# Schematic.net
KiCad netlist of a schematic drawn in EAGLE
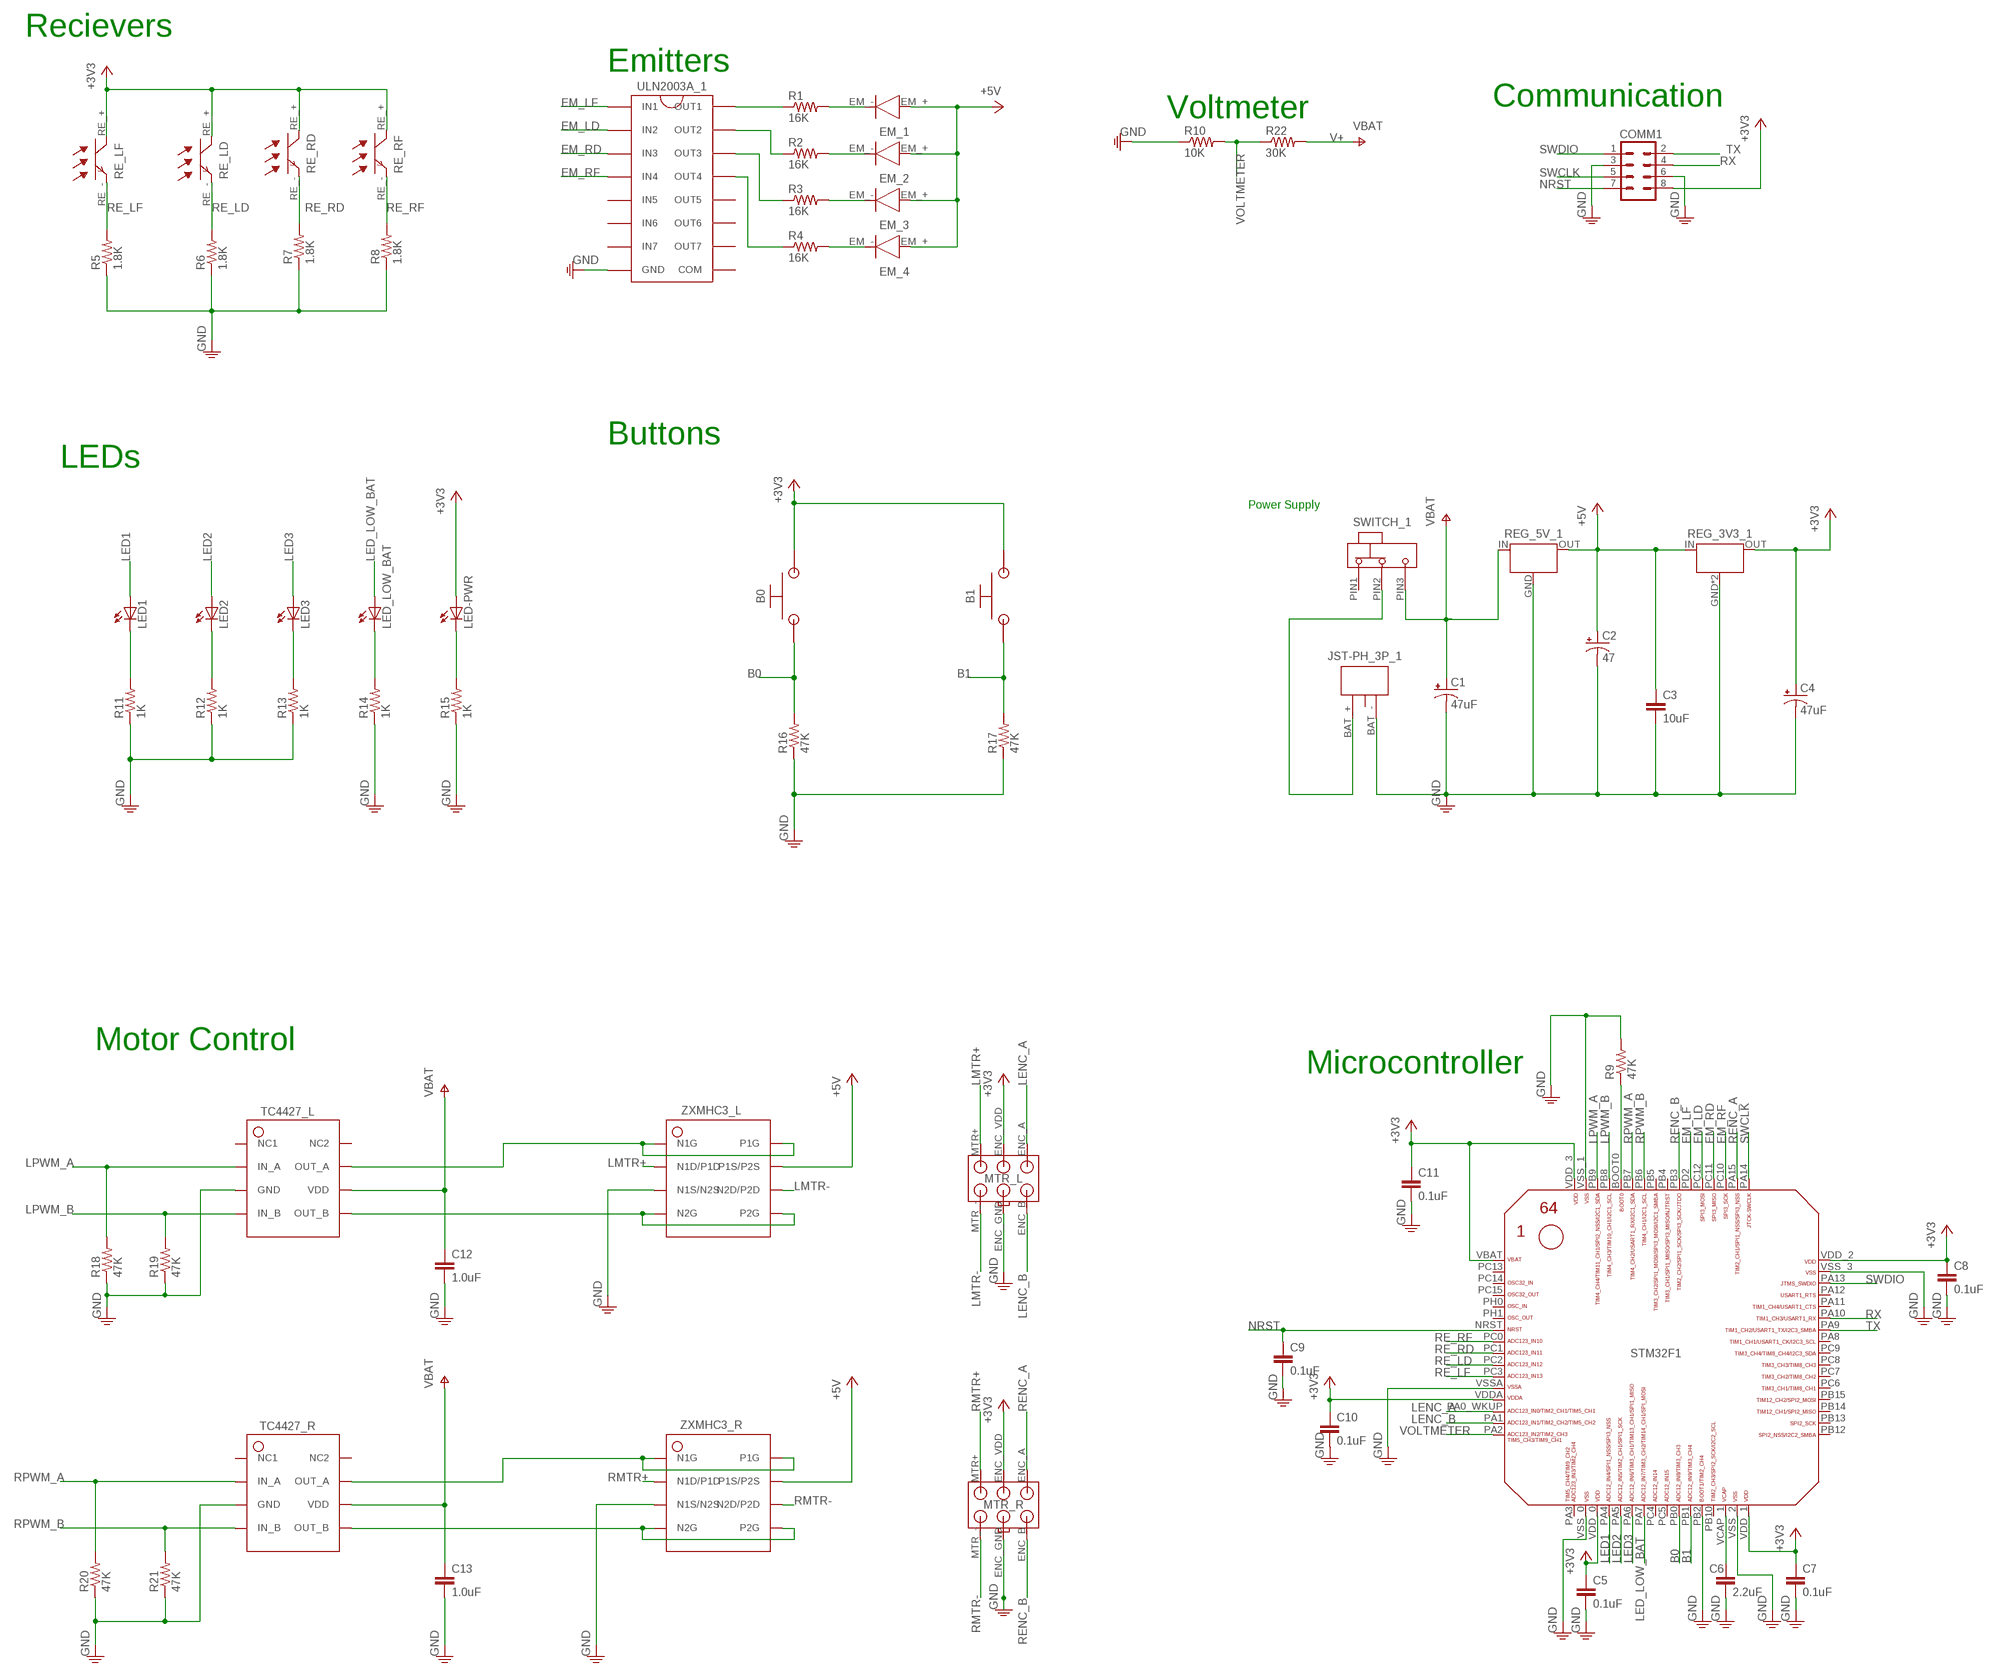
[diagram p0: schematic, sheet 1]

(export (version "E")
  (design (tool "Eeschema 10.0.6"))
  (components
    (comp (ref "B0")
      (value "POLOLU_BUTTON")
      (footprint "eagle-import:POLOLU_BUTTON")
      (libsource (lib "eagle-import") (part "POLOLU_BUTTON"))
    )
    (comp (ref "B1")
      (value "POLOLU_BUTTON")
      (footprint "eagle-import:POLOLU_BUTTON")
      (libsource (lib "eagle-import") (part "POLOLU_BUTTON"))
    )
    (comp (ref "C1")
      (value "47uF")
      (footprint "eagle-import:CAP_TANT_1210IN_3528MM")
      (libsource (lib "eagle-import") (part "CAP_TANT_1210IN_3528MM"))
    )
    (comp (ref "C2")
      (value "47")
      (footprint "eagle-import:CAP_TANT_1210IN_3528MM")
      (libsource (lib "eagle-import") (part "CAP_TANT_1210IN_3528MM"))
    )
    (comp (ref "C3")
      (value "10uF")
      (footprint "eagle-import:0805")
      (libsource (lib "eagle-import") (part "CAP_CERAMIC_0805IN_2012MM"))
    )
    (comp (ref "C4")
      (value "47uF")
      (footprint "eagle-import:CAP_TANT_1210IN_3528MM")
      (libsource (lib "eagle-import") (part "CAP_TANT_1210IN_3528MM"))
    )
    (comp (ref "C5")
      (value "0.1uF")
      (footprint "eagle-import:0805")
      (libsource (lib "eagle-import") (part "CAP_CERAMIC_0805IN_2012MM"))
    )
    (comp (ref "C6")
      (value "2.2uF")
      (footprint "eagle-import:0805")
      (libsource (lib "eagle-import") (part "CAP_CERAMIC_0805IN_2012MM"))
    )
    (comp (ref "C7")
      (value "0.1uF")
      (footprint "eagle-import:0805")
      (libsource (lib "eagle-import") (part "CAP_CERAMIC_0805IN_2012MM"))
    )
    (comp (ref "C8")
      (value "0.1uF")
      (footprint "eagle-import:0805")
      (libsource (lib "eagle-import") (part "CAP_CERAMIC_0805IN_2012MM"))
    )
    (comp (ref "C9")
      (value "0.1uF")
      (footprint "eagle-import:0805")
      (libsource (lib "eagle-import") (part "CAP_CERAMIC_0805IN_2012MM"))
    )
    (comp (ref "C10")
      (value "0.1uF")
      (footprint "eagle-import:0805")
      (libsource (lib "eagle-import") (part "CAP_CERAMIC_0805IN_2012MM"))
    )
    (comp (ref "C11")
      (value "0.1uF")
      (footprint "eagle-import:0805")
      (libsource (lib "eagle-import") (part "CAP_CERAMIC_0805IN_2012MM"))
    )
    (comp (ref "C12")
      (value "1.0uF")
      (footprint "eagle-import:0805")
      (libsource (lib "eagle-import") (part "CAP_CERAMIC_0805IN_2012MM"))
    )
    (comp (ref "C13")
      (value "1.0uF")
      (footprint "eagle-import:0805")
      (libsource (lib "eagle-import") (part "CAP_CERAMIC_0805IN_2012MM"))
    )
    (comp (ref "COMM1")
      (value "M04X2")
      (footprint "eagle-import:2X4")
      (libsource (lib "eagle-import") (part "M04X2"))
    )
    (comp (ref "EM_1")
      (value "SFH4545")
      (footprint "eagle-import:EMITTER")
      (libsource (lib "eagle-import") (part "SFH4545"))
    )
    (comp (ref "EM_2")
      (value "SFH4545")
      (footprint "eagle-import:EMITTER")
      (libsource (lib "eagle-import") (part "SFH4545"))
    )
    (comp (ref "EM_3")
      (value "SFH4545")
      (footprint "eagle-import:EMITTER")
      (libsource (lib "eagle-import") (part "SFH4545"))
    )
    (comp (ref "EM_4")
      (value "SFH4545")
      (footprint "eagle-import:EMITTER")
      (libsource (lib "eagle-import") (part "SFH4545"))
    )
    (comp (ref "JST-PH_3P_1")
      (value "3PIN")
      (footprint "eagle-import:B3B-PH-K-S")
      (libsource (lib "eagle-import") (part "3PIN"))
    )
    (comp (ref "LED-PWR")
      (value "LED")
      (footprint "eagle-import:LED-0805")
      (libsource (lib "eagle-import") (part "LED"))
    )
    (comp (ref "LED1")
      (value "LED")
      (footprint "eagle-import:LED-0805")
      (libsource (lib "eagle-import") (part "LED"))
    )
    (comp (ref "LED2")
      (value "LED")
      (footprint "eagle-import:LED-0805")
      (libsource (lib "eagle-import") (part "LED"))
    )
    (comp (ref "LED3")
      (value "LED")
      (footprint "eagle-import:LED-0805")
      (libsource (lib "eagle-import") (part "LED"))
    )
    (comp (ref "LED_LOW_BAT")
      (value "LED")
      (footprint "eagle-import:LED-0805")
      (libsource (lib "eagle-import") (part "LED"))
    )
    (comp (ref "MTR_L")
      (value "MOTOR_ENCODER_HEADER")
      (footprint "eagle-import:MOTOR_ENCODER_HEADER")
      (libsource (lib "eagle-import") (part "MOTOR_ENCODER_HEADER"))
    )
    (comp (ref "MTR_R")
      (value "MOTOR_ENCODER_HEADER")
      (footprint "eagle-import:MOTOR_ENCODER_HEADER")
      (libsource (lib "eagle-import") (part "MOTOR_ENCODER_HEADER"))
    )
    (comp (ref "R1")
      (value "16K")
      (footprint "eagle-import:0805")
      (libsource (lib "eagle-import") (part "RESISTOR_0805IN_2012MM"))
    )
    (comp (ref "R2")
      (value "16K")
      (footprint "eagle-import:0805")
      (libsource (lib "eagle-import") (part "RESISTOR_0805IN_2012MM"))
    )
    (comp (ref "R3")
      (value "16K")
      (footprint "eagle-import:0805")
      (libsource (lib "eagle-import") (part "RESISTOR_0805IN_2012MM"))
    )
    (comp (ref "R4")
      (value "16K")
      (footprint "eagle-import:0805")
      (libsource (lib "eagle-import") (part "RESISTOR_0805IN_2012MM"))
    )
    (comp (ref "R5")
      (value "1.8K")
      (footprint "eagle-import:0805")
      (libsource (lib "eagle-import") (part "RESISTOR_0805IN_2012MM"))
    )
    (comp (ref "R6")
      (value "1.8K")
      (footprint "eagle-import:0805")
      (libsource (lib "eagle-import") (part "RESISTOR_0805IN_2012MM"))
    )
    (comp (ref "R7")
      (value "1.8K")
      (footprint "eagle-import:0805")
      (libsource (lib "eagle-import") (part "RESISTOR_0805IN_2012MM"))
    )
    (comp (ref "R8")
      (value "1.8K")
      (footprint "eagle-import:0805")
      (libsource (lib "eagle-import") (part "RESISTOR_0805IN_2012MM"))
    )
    (comp (ref "R9")
      (value "47K")
      (footprint "eagle-import:0805")
      (libsource (lib "eagle-import") (part "RESISTOR_0805IN_2012MM"))
    )
    (comp (ref "R10")
      (value "10K")
      (footprint "eagle-import:0805")
      (libsource (lib "eagle-import") (part "RESISTOR_0805IN_2012MM"))
    )
    (comp (ref "R11")
      (value "1K")
      (footprint "eagle-import:0805")
      (libsource (lib "eagle-import") (part "RESISTOR_0805IN_2012MM"))
    )
    (comp (ref "R12")
      (value "1K")
      (footprint "eagle-import:0805")
      (libsource (lib "eagle-import") (part "RESISTOR_0805IN_2012MM"))
    )
    (comp (ref "R13")
      (value "1K")
      (footprint "eagle-import:0805")
      (libsource (lib "eagle-import") (part "RESISTOR_0805IN_2012MM"))
    )
    (comp (ref "R14")
      (value "1K")
      (footprint "eagle-import:0805")
      (libsource (lib "eagle-import") (part "RESISTOR_0805IN_2012MM"))
    )
    (comp (ref "R15")
      (value "1K")
      (footprint "eagle-import:0805")
      (libsource (lib "eagle-import") (part "RESISTOR_0805IN_2012MM"))
    )
    (comp (ref "R16")
      (value "47K")
      (footprint "eagle-import:0805")
      (libsource (lib "eagle-import") (part "RESISTOR_0805IN_2012MM"))
    )
    (comp (ref "R17")
      (value "47K")
      (footprint "eagle-import:0805")
      (libsource (lib "eagle-import") (part "RESISTOR_0805IN_2012MM"))
    )
    (comp (ref "R18")
      (value "47K")
      (footprint "eagle-import:0805")
      (libsource (lib "eagle-import") (part "RESISTOR_0805IN_2012MM"))
    )
    (comp (ref "R19")
      (value "47K")
      (footprint "eagle-import:0805")
      (libsource (lib "eagle-import") (part "RESISTOR_0805IN_2012MM"))
    )
    (comp (ref "R20")
      (value "47K")
      (footprint "eagle-import:0805")
      (libsource (lib "eagle-import") (part "RESISTOR_0805IN_2012MM"))
    )
    (comp (ref "R21")
      (value "47K")
      (footprint "eagle-import:0805")
      (libsource (lib "eagle-import") (part "RESISTOR_0805IN_2012MM"))
    )
    (comp (ref "R22")
      (value "30K")
      (footprint "eagle-import:0805")
      (libsource (lib "eagle-import") (part "RESISTOR_0805IN_2012MM"))
    )
    (comp (ref "REG_3V3_1")
      (value "3V3_REG")
      (footprint "eagle-import:SOT223")
      (libsource (lib "eagle-import") (part "3V3_REG"))
    )
    (comp (ref "REG_5V_1")
      (value "REG_5V_MURATA")
      (footprint "eagle-import:5V_REG_MURATA")
      (libsource (lib "eagle-import") (part "REG_5V_MURATA"))
    )
    (comp (ref "RE_LD")
      (value "TEFT4300")
      (footprint "eagle-import:RECEIVER")
      (libsource (lib "eagle-import") (part "TEFT4300"))
    )
    (comp (ref "RE_LF")
      (value "TEFT4300")
      (footprint "eagle-import:RECEIVER")
      (libsource (lib "eagle-import") (part "TEFT4300"))
    )
    (comp (ref "RE_RD")
      (value "TEFT4300")
      (footprint "eagle-import:RECEIVER")
      (libsource (lib "eagle-import") (part "TEFT4300"))
    )
    (comp (ref "RE_RF")
      (value "TEFT4300")
      (footprint "eagle-import:RECEIVER")
      (libsource (lib "eagle-import") (part "TEFT4300"))
    )
    (comp (ref "STM32F1")
      (value "STM32F4_401_410_411_412_413_446")
      (footprint "eagle-import:LQFP64")
      (libsource (lib "eagle-import") (part "STM32F4_401_410_411_412_413_446"))
    )
    (comp (ref "SWITCH_1")
      (value "POLOLU_SWITCH")
      (footprint "eagle-import:POLOLU_SWITCH")
      (libsource (lib "eagle-import") (part "POLOLU_SWITCH"))
    )
    (comp (ref "TC4427_L")
      (value "TC4427_SOIC8")
      (footprint "eagle-import:TC4427_SOIC8")
      (libsource (lib "eagle-import") (part "TC4427_SOIC8"))
    )
    (comp (ref "TC4427_R")
      (value "TC4427_SOIC8")
      (footprint "eagle-import:TC4427_SOIC8")
      (libsource (lib "eagle-import") (part "TC4427_SOIC8"))
    )
    (comp (ref "ULN2003A_1")
      (value "ULN2003A")
      (footprint "eagle-import:ULN2003A")
      (libsource (lib "eagle-import") (part "ULN2003A"))
    )
    (comp (ref "ZXMHC3_L")
      (value "ZXMHC3")
      (footprint "eagle-import:ZXMHC3")
      (libsource (lib "eagle-import") (part "ZXMHC3"))
    )
    (comp (ref "ZXMHC3_R")
      (value "ZXMHC3")
      (footprint "eagle-import:ZXMHC3")
      (libsource (lib "eagle-import") (part "ZXMHC3"))
    )
  )
  (nets
    (net (code "1") (name "+3V3") (class "Default")
      (node (ref "B0") (pin "P$2") (pinfunction "2_P$2") (pintype "bidirectional"))
      (node (ref "B1") (pin "P$2") (pinfunction "2_P$2") (pintype "bidirectional"))
      (node (ref "C10") (pin "1") (pinfunction "1_1") (pintype "passive"))
      (node (ref "C11") (pin "1") (pinfunction "1_1") (pintype "passive"))
      (node (ref "C4") (pin "A") (pinfunction "+_A") (pintype "passive"))
      (node (ref "C5") (pin "1") (pinfunction "1_1") (pintype "passive"))
      (node (ref "C7") (pin "1") (pinfunction "1_1") (pintype "passive"))
      (node (ref "C8") (pin "1") (pinfunction "1_1") (pintype "passive"))
      (node (ref "COMM1") (pin "8") (pinfunction "8_8") (pintype "passive"))
      (node (ref "LED-PWR") (pin "A") (pinfunction "A_A") (pintype "passive"))
      (node (ref "MTR_L") (pin "ENC_VDD") (pinfunction "ENC_VDD_ENC_VDD") (pintype "power_in"))
      (node (ref "MTR_R") (pin "ENC_VDD") (pinfunction "ENC_VDD_ENC_VDD") (pintype "power_in"))
      (node (ref "REG_3V3_1") (pin "OUT") (pinfunction "OUT_OUT") (pintype "power_in"))
      (node (ref "RE_LD") (pin "RE_+") (pinfunction "C_RE_+") (pintype "bidirectional"))
      (node (ref "RE_LF") (pin "RE_+") (pinfunction "C_RE_+") (pintype "bidirectional"))
      (node (ref "RE_RD") (pin "RE_+") (pinfunction "C_RE_+") (pintype "bidirectional"))
      (node (ref "RE_RF") (pin "RE_+") (pinfunction "C_RE_+") (pintype "bidirectional"))
      (node (ref "STM32F1") (pin "VBAT") (pinfunction "VBAT_VBAT") (pintype "power_in"))
      (node (ref "STM32F1") (pin "VDDA") (pinfunction "VDDA_VDDA") (pintype "power_in"))
      (node (ref "STM32F1") (pin "VDD_0") (pinfunction "VDD_0_VDD_0") (pintype "power_in"))
      (node (ref "STM32F1") (pin "VDD_1") (pinfunction "VDD_1_VDD_1") (pintype "power_in"))
      (node (ref "STM32F1") (pin "VDD_2") (pinfunction "VDD_2_VDD_2") (pintype "power_in"))
      (node (ref "STM32F1") (pin "VDD_3") (pinfunction "VDD_3_VDD_3") (pintype "power_in"))
    )
    (net (code "2") (name "+5V") (class "Default")
      (node (ref "C2") (pin "A") (pinfunction "+_A") (pintype "passive"))
      (node (ref "C3") (pin "1") (pinfunction "1_1") (pintype "passive"))
      (node (ref "EM_1") (pin "EM_+") (pinfunction "+_EM_+") (pintype "bidirectional"))
      (node (ref "EM_2") (pin "EM_+") (pinfunction "+_EM_+") (pintype "bidirectional"))
      (node (ref "EM_3") (pin "EM_+") (pinfunction "+_EM_+") (pintype "bidirectional"))
      (node (ref "EM_4") (pin "EM_+") (pinfunction "+_EM_+") (pintype "bidirectional"))
      (node (ref "REG_3V3_1") (pin "IN") (pinfunction "IN_IN") (pintype "power_in"))
      (node (ref "REG_5V_1") (pin "OUT") (pinfunction "OUT_OUT") (pintype "power_in"))
      (node (ref "ZXMHC3_L") (pin "P1S/P2S") (pinfunction "P1S/P2S_P1S/P2S") (pintype "bidirectional"))
      (node (ref "ZXMHC3_R") (pin "P1S/P2S") (pinfunction "P1S/P2S_P1S/P2S") (pintype "bidirectional"))
    )
    (net (code "3") (name "/B0") (class "Default")
      (node (ref "B0") (pin "P$1") (pinfunction "1_P$1") (pintype "bidirectional"))
      (node (ref "R16") (pin "2") (pinfunction "2_2") (pintype "passive"))
      (node (ref "STM32F1") (pin "PB0") (pinfunction "PB0_PB0") (pintype "bidirectional"))
    )
    (net (code "4") (name "/B1") (class "Default")
      (node (ref "B1") (pin "P$1") (pinfunction "1_P$1") (pintype "bidirectional"))
      (node (ref "R17") (pin "2") (pinfunction "2_2") (pintype "passive"))
      (node (ref "STM32F1") (pin "PB1") (pinfunction "PB1_PB1") (pintype "bidirectional"))
    )
    (net (code "5") (name "/EM_LD") (class "Default")
      (node (ref "STM32F1") (pin "PC12") (pinfunction "PC12_PC12") (pintype "bidirectional"))
      (node (ref "ULN2003A_1") (pin "2B") (pinfunction "IN2_2B") (pintype "bidirectional"))
    )
    (net (code "6") (name "/EM_LF") (class "Default")
      (node (ref "STM32F1") (pin "PD2") (pinfunction "PD2_PD2") (pintype "bidirectional"))
      (node (ref "ULN2003A_1") (pin "1B") (pinfunction "IN1_1B") (pintype "bidirectional"))
    )
    (net (code "7") (name "/EM_RD") (class "Default")
      (node (ref "STM32F1") (pin "PC11") (pinfunction "PC11_PC11") (pintype "bidirectional"))
      (node (ref "ULN2003A_1") (pin "3B") (pinfunction "IN3_3B") (pintype "bidirectional"))
    )
    (net (code "8") (name "/EM_RF") (class "Default")
      (node (ref "STM32F1") (pin "PC10") (pinfunction "PC10_PC10") (pintype "bidirectional"))
      (node (ref "ULN2003A_1") (pin "4B") (pinfunction "IN4_4B") (pintype "bidirectional"))
    )
    (net (code "9") (name "/LED1") (class "Default")
      (node (ref "LED1") (pin "A") (pinfunction "A_A") (pintype "passive"))
      (node (ref "STM32F1") (pin "PA4") (pinfunction "PA4_PA4") (pintype "bidirectional"))
    )
    (net (code "10") (name "/LED2") (class "Default")
      (node (ref "LED2") (pin "A") (pinfunction "A_A") (pintype "passive"))
      (node (ref "STM32F1") (pin "PA5") (pinfunction "PA5_PA5") (pintype "bidirectional"))
    )
    (net (code "11") (name "/LED3") (class "Default")
      (node (ref "LED3") (pin "A") (pinfunction "A_A") (pintype "passive"))
      (node (ref "STM32F1") (pin "PA6") (pinfunction "PA6_PA6") (pintype "bidirectional"))
    )
    (net (code "12") (name "/LED_LOW_BAT") (class "Default")
      (node (ref "LED_LOW_BAT") (pin "A") (pinfunction "A_A") (pintype "passive"))
      (node (ref "STM32F1") (pin "PA7") (pinfunction "PA7_PA7") (pintype "bidirectional"))
    )
    (net (code "13") (name "/LENC_A") (class "Default")
      (node (ref "MTR_L") (pin "ENC_A") (pinfunction "ENC_A_ENC_A") (pintype "output"))
      (node (ref "STM32F1") (pin "PA0_WKUP") (pinfunction "PA0_AKUP_PA0_WKUP") (pintype "bidirectional"))
    )
    (net (code "14") (name "/LENC_B") (class "Default")
      (node (ref "MTR_L") (pin "ENC_B") (pinfunction "ENC_B_ENC_B") (pintype "output"))
      (node (ref "STM32F1") (pin "PA1") (pinfunction "PA1_PA1") (pintype "bidirectional"))
    )
    (net (code "15") (name "/LMTR+") (class "Default")
      (node (ref "MTR_L") (pin "MTR+") (pinfunction "MTR_+_MTR+") (pintype "input"))
      (node (ref "ZXMHC3_L") (pin "N1D/P1D") (pinfunction "N1D/P1D_N1D/P1D") (pintype "bidirectional"))
    )
    (net (code "16") (name "/LMTR-") (class "Default")
      (node (ref "MTR_L") (pin "MTR_-") (pinfunction "MTR_-_MTR_-") (pintype "input"))
      (node (ref "ZXMHC3_L") (pin "N2D/P2D") (pinfunction "N2D/P2D_N2D/P2D") (pintype "bidirectional"))
    )
    (net (code "17") (name "/LPWM_A") (class "Default")
      (node (ref "R18") (pin "2") (pinfunction "2_2") (pintype "passive"))
      (node (ref "STM32F1") (pin "PB9") (pinfunction "PB9_PB9") (pintype "bidirectional"))
      (node (ref "TC4427_L") (pin "IN_A") (pinfunction "IN_A_IN_A") (pintype "bidirectional"))
    )
    (net (code "18") (name "/LPWM_B") (class "Default")
      (node (ref "R19") (pin "2") (pinfunction "2_2") (pintype "passive"))
      (node (ref "STM32F1") (pin "PB8") (pinfunction "PB8_PB8") (pintype "bidirectional"))
      (node (ref "TC4427_L") (pin "IN_B") (pinfunction "IN_B_IN_B") (pintype "bidirectional"))
    )
    (net (code "19") (name "/NRST") (class "Default")
      (node (ref "C9") (pin "1") (pinfunction "1_1") (pintype "passive"))
      (node (ref "COMM1") (pin "7") (pinfunction "7_7") (pintype "passive"))
      (node (ref "STM32F1") (pin "NRST") (pinfunction "NRST_NRST") (pintype "bidirectional"))
    )
    (net (code "20") (name "/RENC_A") (class "Default")
      (node (ref "MTR_R") (pin "ENC_A") (pinfunction "ENC_A_ENC_A") (pintype "output"))
      (node (ref "STM32F1") (pin "PA15") (pinfunction "PA15_PA15") (pintype "bidirectional"))
    )
    (net (code "21") (name "/RENC_B") (class "Default")
      (node (ref "MTR_R") (pin "ENC_B") (pinfunction "ENC_B_ENC_B") (pintype "output"))
      (node (ref "STM32F1") (pin "PB3") (pinfunction "PB3_PB3") (pintype "bidirectional"))
    )
    (net (code "22") (name "/RE_LD") (class "Default")
      (node (ref "R6") (pin "2") (pinfunction "2_2") (pintype "passive"))
      (node (ref "RE_LD") (pin "RE_-") (pinfunction "E_RE_-") (pintype "bidirectional"))
      (node (ref "STM32F1") (pin "PC2") (pinfunction "PC2_PC2") (pintype "bidirectional"))
    )
    (net (code "23") (name "/RE_LF") (class "Default")
      (node (ref "R5") (pin "2") (pinfunction "2_2") (pintype "passive"))
      (node (ref "RE_LF") (pin "RE_-") (pinfunction "E_RE_-") (pintype "bidirectional"))
      (node (ref "STM32F1") (pin "PC3") (pinfunction "PC3_PC3") (pintype "bidirectional"))
    )
    (net (code "24") (name "/RE_RD") (class "Default")
      (node (ref "R7") (pin "2") (pinfunction "2_2") (pintype "passive"))
      (node (ref "RE_RD") (pin "RE_-") (pinfunction "E_RE_-") (pintype "bidirectional"))
      (node (ref "STM32F1") (pin "PC1") (pinfunction "PC1_PC1") (pintype "bidirectional"))
    )
    (net (code "25") (name "/RE_RF") (class "Default")
      (node (ref "R8") (pin "2") (pinfunction "2_2") (pintype "passive"))
      (node (ref "RE_RF") (pin "RE_-") (pinfunction "E_RE_-") (pintype "bidirectional"))
      (node (ref "STM32F1") (pin "PC0") (pinfunction "PC0_PC0") (pintype "bidirectional"))
    )
    (net (code "26") (name "/RMTR+") (class "Default")
      (node (ref "MTR_R") (pin "MTR+") (pinfunction "MTR_+_MTR+") (pintype "input"))
      (node (ref "ZXMHC3_R") (pin "N1D/P1D") (pinfunction "N1D/P1D_N1D/P1D") (pintype "bidirectional"))
    )
    (net (code "27") (name "/RMTR-") (class "Default")
      (node (ref "MTR_R") (pin "MTR_-") (pinfunction "MTR_-_MTR_-") (pintype "input"))
      (node (ref "ZXMHC3_R") (pin "N2D/P2D") (pinfunction "N2D/P2D_N2D/P2D") (pintype "bidirectional"))
    )
    (net (code "28") (name "/RPWM_A") (class "Default")
      (node (ref "R20") (pin "2") (pinfunction "2_2") (pintype "passive"))
      (node (ref "STM32F1") (pin "PB7") (pinfunction "PB7_PB7") (pintype "bidirectional"))
      (node (ref "TC4427_R") (pin "IN_A") (pinfunction "IN_A_IN_A") (pintype "bidirectional"))
    )
    (net (code "29") (name "/RPWM_B") (class "Default")
      (node (ref "R21") (pin "2") (pinfunction "2_2") (pintype "passive"))
      (node (ref "STM32F1") (pin "PB6") (pinfunction "PB6_PB6") (pintype "bidirectional"))
      (node (ref "TC4427_R") (pin "IN_B") (pinfunction "IN_B_IN_B") (pintype "bidirectional"))
    )
    (net (code "30") (name "/RX") (class "Default")
      (node (ref "COMM1") (pin "4") (pinfunction "4_4") (pintype "passive"))
      (node (ref "STM32F1") (pin "PA10") (pinfunction "PA10_PA10") (pintype "bidirectional"))
    )
    (net (code "31") (name "/SWCLK") (class "Default")
      (node (ref "COMM1") (pin "5") (pinfunction "5_5") (pintype "passive"))
      (node (ref "STM32F1") (pin "PA14") (pinfunction "PA14_PA14") (pintype "bidirectional"))
    )
    (net (code "32") (name "/SWDIO") (class "Default")
      (node (ref "COMM1") (pin "1") (pinfunction "1_1") (pintype "passive"))
      (node (ref "STM32F1") (pin "PA13") (pinfunction "PA13_PA13") (pintype "bidirectional"))
    )
    (net (code "33") (name "/TX") (class "Default")
      (node (ref "COMM1") (pin "2") (pinfunction "2_2") (pintype "passive"))
      (node (ref "STM32F1") (pin "PA9") (pinfunction "PA9_PA9") (pintype "bidirectional"))
    )
    (net (code "34") (name "/VOLTMETER") (class "Default")
      (node (ref "R10") (pin "2") (pinfunction "2_2") (pintype "passive"))
      (node (ref "R22") (pin "1") (pinfunction "1_1") (pintype "passive"))
      (node (ref "STM32F1") (pin "PA2") (pinfunction "PA2_PA2") (pintype "bidirectional"))
    )
    (net (code "35") (name "GND") (class "Default")
      (node (ref "C1") (pin "C") (pinfunction "-_C") (pintype "passive"))
      (node (ref "C10") (pin "2") (pinfunction "2_2") (pintype "passive"))
      (node (ref "C11") (pin "2") (pinfunction "2_2") (pintype "passive"))
      (node (ref "C12") (pin "2") (pinfunction "2_2") (pintype "passive"))
      (node (ref "C13") (pin "2") (pinfunction "2_2") (pintype "passive"))
      (node (ref "C2") (pin "C") (pinfunction "-_C") (pintype "passive"))
      (node (ref "C3") (pin "2") (pinfunction "2_2") (pintype "passive"))
      (node (ref "C4") (pin "C") (pinfunction "-_C") (pintype "passive"))
      (node (ref "C5") (pin "2") (pinfunction "2_2") (pintype "passive"))
      (node (ref "C6") (pin "2") (pinfunction "2_2") (pintype "passive"))
      (node (ref "C7") (pin "2") (pinfunction "2_2") (pintype "passive"))
      (node (ref "C8") (pin "2") (pinfunction "2_2") (pintype "passive"))
      (node (ref "C9") (pin "2") (pinfunction "2_2") (pintype "passive"))
      (node (ref "COMM1") (pin "3") (pinfunction "3_3") (pintype "passive"))
      (node (ref "COMM1") (pin "6") (pinfunction "6_6") (pintype "passive"))
      (node (ref "JST-PH_3P_1") (pin "BAT_-") (pinfunction "BAT_-_BAT_-") (pintype "bidirectional"))
      (node (ref "MTR_L") (pin "ENC_GND") (pinfunction "ENC_GND_ENC_GND") (pintype "power_in"))
      (node (ref "MTR_R") (pin "ENC_GND") (pinfunction "ENC_GND_ENC_GND") (pintype "power_in"))
      (node (ref "R10") (pin "1") (pinfunction "1_1") (pintype "passive"))
      (node (ref "R11") (pin "1") (pinfunction "1_1") (pintype "passive"))
      (node (ref "R12") (pin "1") (pinfunction "1_1") (pintype "passive"))
      (node (ref "R13") (pin "1") (pinfunction "1_1") (pintype "passive"))
      (node (ref "R14") (pin "1") (pinfunction "1_1") (pintype "passive"))
      (node (ref "R15") (pin "1") (pinfunction "1_1") (pintype "passive"))
      (node (ref "R16") (pin "1") (pinfunction "1_1") (pintype "passive"))
      (node (ref "R17") (pin "1") (pinfunction "1_1") (pintype "passive"))
      (node (ref "R18") (pin "1") (pinfunction "1_1") (pintype "passive"))
      (node (ref "R19") (pin "1") (pinfunction "1_1") (pintype "passive"))
      (node (ref "R20") (pin "1") (pinfunction "1_1") (pintype "passive"))
      (node (ref "R21") (pin "1") (pinfunction "1_1") (pintype "passive"))
      (node (ref "R5") (pin "1") (pinfunction "1_1") (pintype "passive"))
      (node (ref "R6") (pin "1") (pinfunction "1_1") (pintype "passive"))
      (node (ref "R7") (pin "1") (pinfunction "1_1") (pintype "passive"))
      (node (ref "R8") (pin "1") (pinfunction "1_1") (pintype "passive"))
      (node (ref "R9") (pin "2") (pinfunction "2_2") (pintype "passive"))
      (node (ref "REG_3V3_1") (pin "GND") (pinfunction "GND_GND") (pintype "power_in"))
      (node (ref "REG_3V3_1") (pin "GND2") (pinfunction "GND_GND2") (pintype "power_in"))
      (node (ref "REG_5V_1") (pin "GND") (pinfunction "GND_GND") (pintype "power_in"))
      (node (ref "STM32F1") (pin "PB2") (pinfunction "PB2_PB2") (pintype "bidirectional"))
      (node (ref "STM32F1") (pin "VSSA") (pinfunction "VSSA_VSSA") (pintype "power_in"))
      (node (ref "STM32F1") (pin "VSS_0") (pinfunction "VSS_0_VSS_0") (pintype "power_in"))
      (node (ref "STM32F1") (pin "VSS_1") (pinfunction "VSS_1_VSS_1") (pintype "power_in"))
      (node (ref "STM32F1") (pin "VSS_2") (pinfunction "VCAP_1_VSS_2") (pintype "power_in"))
      (node (ref "STM32F1") (pin "VSS_3") (pinfunction "VCAP_2_VSS_3") (pintype "power_in"))
      (node (ref "TC4427_L") (pin "GND") (pinfunction "GND_GND") (pintype "power_in"))
      (node (ref "TC4427_R") (pin "GND") (pinfunction "GND_GND") (pintype "power_in"))
      (node (ref "ULN2003A_1") (pin "GND") (pinfunction "GND_GND") (pintype "power_in"))
      (node (ref "ZXMHC3_L") (pin "N1S/N2S") (pinfunction "N1S/N2S_N1S/N2S") (pintype "bidirectional"))
      (node (ref "ZXMHC3_R") (pin "N1S/N2S") (pinfunction "N1S/N2S_N1S/N2S") (pintype "bidirectional"))
    )
    (net (code "36") (name "Net-(EM_1--)") (class "Default")
      (node (ref "EM_1") (pin "EM_-") (pinfunction "-_EM_-") (pintype "bidirectional"))
      (node (ref "R1") (pin "2") (pinfunction "2_2") (pintype "passive"))
    )
    (net (code "37") (name "Net-(EM_2--)") (class "Default")
      (node (ref "EM_2") (pin "EM_-") (pinfunction "-_EM_-") (pintype "bidirectional"))
      (node (ref "R2") (pin "2") (pinfunction "2_2") (pintype "passive"))
    )
    (net (code "38") (name "Net-(EM_3--)") (class "Default")
      (node (ref "EM_3") (pin "EM_-") (pinfunction "-_EM_-") (pintype "bidirectional"))
      (node (ref "R3") (pin "2") (pinfunction "2_2") (pintype "passive"))
    )
    (net (code "39") (name "Net-(EM_4--)") (class "Default")
      (node (ref "EM_4") (pin "EM_-") (pinfunction "-_EM_-") (pintype "bidirectional"))
      (node (ref "R4") (pin "2") (pinfunction "2_2") (pintype "passive"))
    )
    (net (code "40") (name "Net-(JST-PH_3P_1-PadBAT_+)") (class "Default")
      (node (ref "JST-PH_3P_1") (pin "BAT_+") (pinfunction "BAT_+_BAT_+") (pintype "bidirectional"))
      (node (ref "SWITCH_1") (pin "PIN2") (pinfunction "PIN2_PIN2") (pintype "bidirectional"))
    )
    (net (code "41") (name "Net-(LED-PWR-PadC)") (class "Default")
      (node (ref "LED-PWR") (pin "C") (pinfunction "C_C") (pintype "passive"))
      (node (ref "R15") (pin "2") (pinfunction "2_2") (pintype "passive"))
    )
    (net (code "42") (name "Net-(LED1-PadC)") (class "Default")
      (node (ref "LED1") (pin "C") (pinfunction "C_C") (pintype "passive"))
      (node (ref "R11") (pin "2") (pinfunction "2_2") (pintype "passive"))
    )
    (net (code "43") (name "Net-(LED2-PadC)") (class "Default")
      (node (ref "LED2") (pin "C") (pinfunction "C_C") (pintype "passive"))
      (node (ref "R12") (pin "2") (pinfunction "2_2") (pintype "passive"))
    )
    (net (code "44") (name "Net-(LED3-PadC)") (class "Default")
      (node (ref "LED3") (pin "C") (pinfunction "C_C") (pintype "passive"))
      (node (ref "R13") (pin "2") (pinfunction "2_2") (pintype "passive"))
    )
    (net (code "45") (name "Net-(LED_LOW_BAT-PadC)") (class "Default")
      (node (ref "LED_LOW_BAT") (pin "C") (pinfunction "C_C") (pintype "passive"))
      (node (ref "R14") (pin "2") (pinfunction "2_2") (pintype "passive"))
    )
    (net (code "46") (name "Net-(R9-Pad1)") (class "Default")
      (node (ref "R9") (pin "1") (pinfunction "1_1") (pintype "passive"))
      (node (ref "STM32F1") (pin "BOOT0") (pinfunction "BOOT0_BOOT0") (pintype "bidirectional"))
    )
    (net (code "47") (name "Net-(STM32F1-PB11)") (class "Default")
      (node (ref "C6") (pin "1") (pinfunction "1_1") (pintype "passive"))
      (node (ref "STM32F1") (pin "VCAP_1") (pinfunction "PB11_VCAP_1") (pintype "bidirectional"))
    )
    (net (code "48") (name "Net-(TC4427_L-PadOUT_A)") (class "Default")
      (node (ref "TC4427_L") (pin "OUT_A") (pinfunction "OUT_A_OUT_A") (pintype "bidirectional"))
      (node (ref "ZXMHC3_L") (pin "N1G") (pinfunction "N1G_N1G") (pintype "bidirectional"))
      (node (ref "ZXMHC3_L") (pin "P1G") (pinfunction "P1G_P1G") (pintype "bidirectional"))
    )
    (net (code "49") (name "Net-(TC4427_L-PadOUT_B)") (class "Default")
      (node (ref "TC4427_L") (pin "OUT_B") (pinfunction "OUT_B_OUT_B") (pintype "bidirectional"))
      (node (ref "ZXMHC3_L") (pin "N2G") (pinfunction "N2G_N2G") (pintype "bidirectional"))
      (node (ref "ZXMHC3_L") (pin "P2G") (pinfunction "P2G_P2G") (pintype "bidirectional"))
    )
    (net (code "50") (name "Net-(TC4427_R-PadOUT_A)") (class "Default")
      (node (ref "TC4427_R") (pin "OUT_A") (pinfunction "OUT_A_OUT_A") (pintype "bidirectional"))
      (node (ref "ZXMHC3_R") (pin "N1G") (pinfunction "N1G_N1G") (pintype "bidirectional"))
      (node (ref "ZXMHC3_R") (pin "P1G") (pinfunction "P1G_P1G") (pintype "bidirectional"))
    )
    (net (code "51") (name "Net-(TC4427_R-PadOUT_B)") (class "Default")
      (node (ref "TC4427_R") (pin "OUT_B") (pinfunction "OUT_B_OUT_B") (pintype "bidirectional"))
      (node (ref "ZXMHC3_R") (pin "N2G") (pinfunction "N2G_N2G") (pintype "bidirectional"))
      (node (ref "ZXMHC3_R") (pin "P2G") (pinfunction "P2G_P2G") (pintype "bidirectional"))
    )
    (net (code "52") (name "Net-(ULN2003A_1-OUT1)") (class "Default")
      (node (ref "R1") (pin "1") (pinfunction "1_1") (pintype "passive"))
      (node (ref "ULN2003A_1") (pin "1C") (pinfunction "OUT1_1C") (pintype "bidirectional"))
    )
    (net (code "53") (name "Net-(ULN2003A_1-OUT2)") (class "Default")
      (node (ref "R2") (pin "1") (pinfunction "1_1") (pintype "passive"))
      (node (ref "ULN2003A_1") (pin "2C") (pinfunction "OUT2_2C") (pintype "bidirectional"))
    )
    (net (code "54") (name "Net-(ULN2003A_1-OUT3)") (class "Default")
      (node (ref "R3") (pin "1") (pinfunction "1_1") (pintype "passive"))
      (node (ref "ULN2003A_1") (pin "3C") (pinfunction "OUT3_3C") (pintype "bidirectional"))
    )
    (net (code "55") (name "Net-(ULN2003A_1-OUT4)") (class "Default")
      (node (ref "R4") (pin "1") (pinfunction "1_1") (pintype "passive"))
      (node (ref "ULN2003A_1") (pin "4C") (pinfunction "OUT4_4C") (pintype "bidirectional"))
    )
    (net (code "56") (name "VBAT") (class "Default")
      (node (ref "C1") (pin "A") (pinfunction "+_A") (pintype "passive"))
      (node (ref "C12") (pin "1") (pinfunction "1_1") (pintype "passive"))
      (node (ref "C13") (pin "1") (pinfunction "1_1") (pintype "passive"))
      (node (ref "R22") (pin "2") (pinfunction "2_2") (pintype "passive"))
      (node (ref "REG_5V_1") (pin "IN") (pinfunction "IN_IN") (pintype "power_in"))
      (node (ref "SWITCH_1") (pin "PIN3") (pinfunction "PIN3_PIN3") (pintype "bidirectional"))
      (node (ref "TC4427_L") (pin "VDD") (pinfunction "VDD_VDD") (pintype "power_in"))
      (node (ref "TC4427_R") (pin "VDD") (pinfunction "VDD_VDD") (pintype "power_in"))
    )
    (net (code "57") (name "unconnected-(STM32F1-PadPA3)") (class "Default")
      (node (ref "STM32F1") (pin "PA3") (pinfunction "PA3_PA3") (pintype "bidirectional"))
    )
    (net (code "58") (name "unconnected-(STM32F1-PadPA8)") (class "Default")
      (node (ref "STM32F1") (pin "PA8") (pinfunction "PA8_PA8") (pintype "bidirectional"))
    )
    (net (code "59") (name "unconnected-(STM32F1-PadPA11)") (class "Default")
      (node (ref "STM32F1") (pin "PA11") (pinfunction "PA11_PA11") (pintype "bidirectional"))
    )
    (net (code "60") (name "unconnected-(STM32F1-PadPA12)") (class "Default")
      (node (ref "STM32F1") (pin "PA12") (pinfunction "PA12_PA12") (pintype "bidirectional"))
    )
    (net (code "61") (name "unconnected-(STM32F1-PadPB4)") (class "Default")
      (node (ref "STM32F1") (pin "PB4") (pinfunction "PB4_PB4") (pintype "bidirectional"))
    )
    (net (code "62") (name "unconnected-(STM32F1-PadPB5)") (class "Default")
      (node (ref "STM32F1") (pin "PB5") (pinfunction "PB5_PB5") (pintype "bidirectional"))
    )
    (net (code "63") (name "unconnected-(STM32F1-PadPB10)") (class "Default")
      (node (ref "STM32F1") (pin "PB10") (pinfunction "PB10_PB10") (pintype "bidirectional"))
    )
    (net (code "64") (name "unconnected-(STM32F1-PadPB12)") (class "Default")
      (node (ref "STM32F1") (pin "PB12") (pinfunction "PB12_PB12") (pintype "bidirectional"))
    )
    (net (code "65") (name "unconnected-(STM32F1-PadPB13)") (class "Default")
      (node (ref "STM32F1") (pin "PB13") (pinfunction "PB13_PB13") (pintype "bidirectional"))
    )
    (net (code "66") (name "unconnected-(STM32F1-PadPB14)") (class "Default")
      (node (ref "STM32F1") (pin "PB14") (pinfunction "PB14_PB14") (pintype "bidirectional"))
    )
    (net (code "67") (name "unconnected-(STM32F1-PadPB15)") (class "Default")
      (node (ref "STM32F1") (pin "PB15") (pinfunction "PB15_PB15") (pintype "bidirectional"))
    )
    (net (code "68") (name "unconnected-(STM32F1-PadPC4)") (class "Default")
      (node (ref "STM32F1") (pin "PC4") (pinfunction "PC4_PC4") (pintype "bidirectional"))
    )
    (net (code "69") (name "unconnected-(STM32F1-PadPC5)") (class "Default")
      (node (ref "STM32F1") (pin "PC5") (pinfunction "PC5_PC5") (pintype "bidirectional"))
    )
    (net (code "70") (name "unconnected-(STM32F1-PadPC6)") (class "Default")
      (node (ref "STM32F1") (pin "PC6") (pinfunction "PC6_PC6") (pintype "bidirectional"))
    )
    (net (code "71") (name "unconnected-(STM32F1-PadPC7)") (class "Default")
      (node (ref "STM32F1") (pin "PC7") (pinfunction "PC7_PC7") (pintype "bidirectional"))
    )
    (net (code "72") (name "unconnected-(STM32F1-PadPC8)") (class "Default")
      (node (ref "STM32F1") (pin "PC8") (pinfunction "PC8_PC8") (pintype "bidirectional"))
    )
    (net (code "73") (name "unconnected-(STM32F1-PadPC9)") (class "Default")
      (node (ref "STM32F1") (pin "PC9") (pinfunction "PC9_PC9") (pintype "bidirectional"))
    )
    (net (code "74") (name "unconnected-(STM32F1-PadPC13)") (class "Default")
      (node (ref "STM32F1") (pin "PC13") (pinfunction "PC13_PC13") (pintype "bidirectional"))
    )
    (net (code "75") (name "unconnected-(STM32F1-PadPC14)") (class "Default")
      (node (ref "STM32F1") (pin "PC14") (pinfunction "PC14_PC14") (pintype "bidirectional"))
    )
    (net (code "76") (name "unconnected-(STM32F1-PadPC15)") (class "Default")
      (node (ref "STM32F1") (pin "PC15") (pinfunction "PC15_PC15") (pintype "bidirectional"))
    )
    (net (code "77") (name "unconnected-(STM32F1-PadPH0)") (class "Default")
      (node (ref "STM32F1") (pin "PH0") (pinfunction "PH0_PH0") (pintype "bidirectional"))
    )
    (net (code "78") (name "unconnected-(STM32F1-PadPH1)") (class "Default")
      (node (ref "STM32F1") (pin "PH1") (pinfunction "PH1_PH1") (pintype "bidirectional"))
    )
    (net (code "79") (name "unconnected-(SWITCH_1-PadPIN1)") (class "Default")
      (node (ref "SWITCH_1") (pin "PIN1") (pinfunction "PIN1_PIN1") (pintype "bidirectional"))
    )
    (net (code "80") (name "unconnected-(TC4427_L-PadNC1)") (class "Default")
      (node (ref "TC4427_L") (pin "NC1") (pinfunction "NC1_NC1") (pintype "bidirectional"))
    )
    (net (code "81") (name "unconnected-(TC4427_L-PadNC2)") (class "Default")
      (node (ref "TC4427_L") (pin "NC2") (pinfunction "NC2_NC2") (pintype "bidirectional"))
    )
    (net (code "82") (name "unconnected-(TC4427_R-PadNC1)") (class "Default")
      (node (ref "TC4427_R") (pin "NC1") (pinfunction "NC1_NC1") (pintype "bidirectional"))
    )
    (net (code "83") (name "unconnected-(TC4427_R-PadNC2)") (class "Default")
      (node (ref "TC4427_R") (pin "NC2") (pinfunction "NC2_NC2") (pintype "bidirectional"))
    )
    (net (code "84") (name "unconnected-(ULN2003A_1-IN5-Pad5B)") (class "Default")
      (node (ref "ULN2003A_1") (pin "5B") (pinfunction "IN5_5B") (pintype "bidirectional"))
    )
    (net (code "85") (name "unconnected-(ULN2003A_1-IN6-Pad6B)") (class "Default")
      (node (ref "ULN2003A_1") (pin "6B") (pinfunction "IN6_6B") (pintype "bidirectional"))
    )
    (net (code "86") (name "unconnected-(ULN2003A_1-IN7-Pad7B)") (class "Default")
      (node (ref "ULN2003A_1") (pin "7B") (pinfunction "IN7_7B") (pintype "bidirectional"))
    )
    (net (code "87") (name "unconnected-(ULN2003A_1-OUT5-Pad5C)") (class "Default")
      (node (ref "ULN2003A_1") (pin "5C") (pinfunction "OUT5_5C") (pintype "bidirectional"))
    )
    (net (code "88") (name "unconnected-(ULN2003A_1-OUT6-Pad6C)") (class "Default")
      (node (ref "ULN2003A_1") (pin "6C") (pinfunction "OUT6_6C") (pintype "bidirectional"))
    )
    (net (code "89") (name "unconnected-(ULN2003A_1-OUT7-Pad7C)") (class "Default")
      (node (ref "ULN2003A_1") (pin "7C") (pinfunction "OUT7_7C") (pintype "bidirectional"))
    )
    (net (code "90") (name "unconnected-(ULN2003A_1-PadCOM)") (class "Default")
      (node (ref "ULN2003A_1") (pin "COM") (pinfunction "COM_COM") (pintype "bidirectional"))
    )
  )
)
